# LCD_Controller.net
KiCad netlist of a schematic drawn in Altium Designer
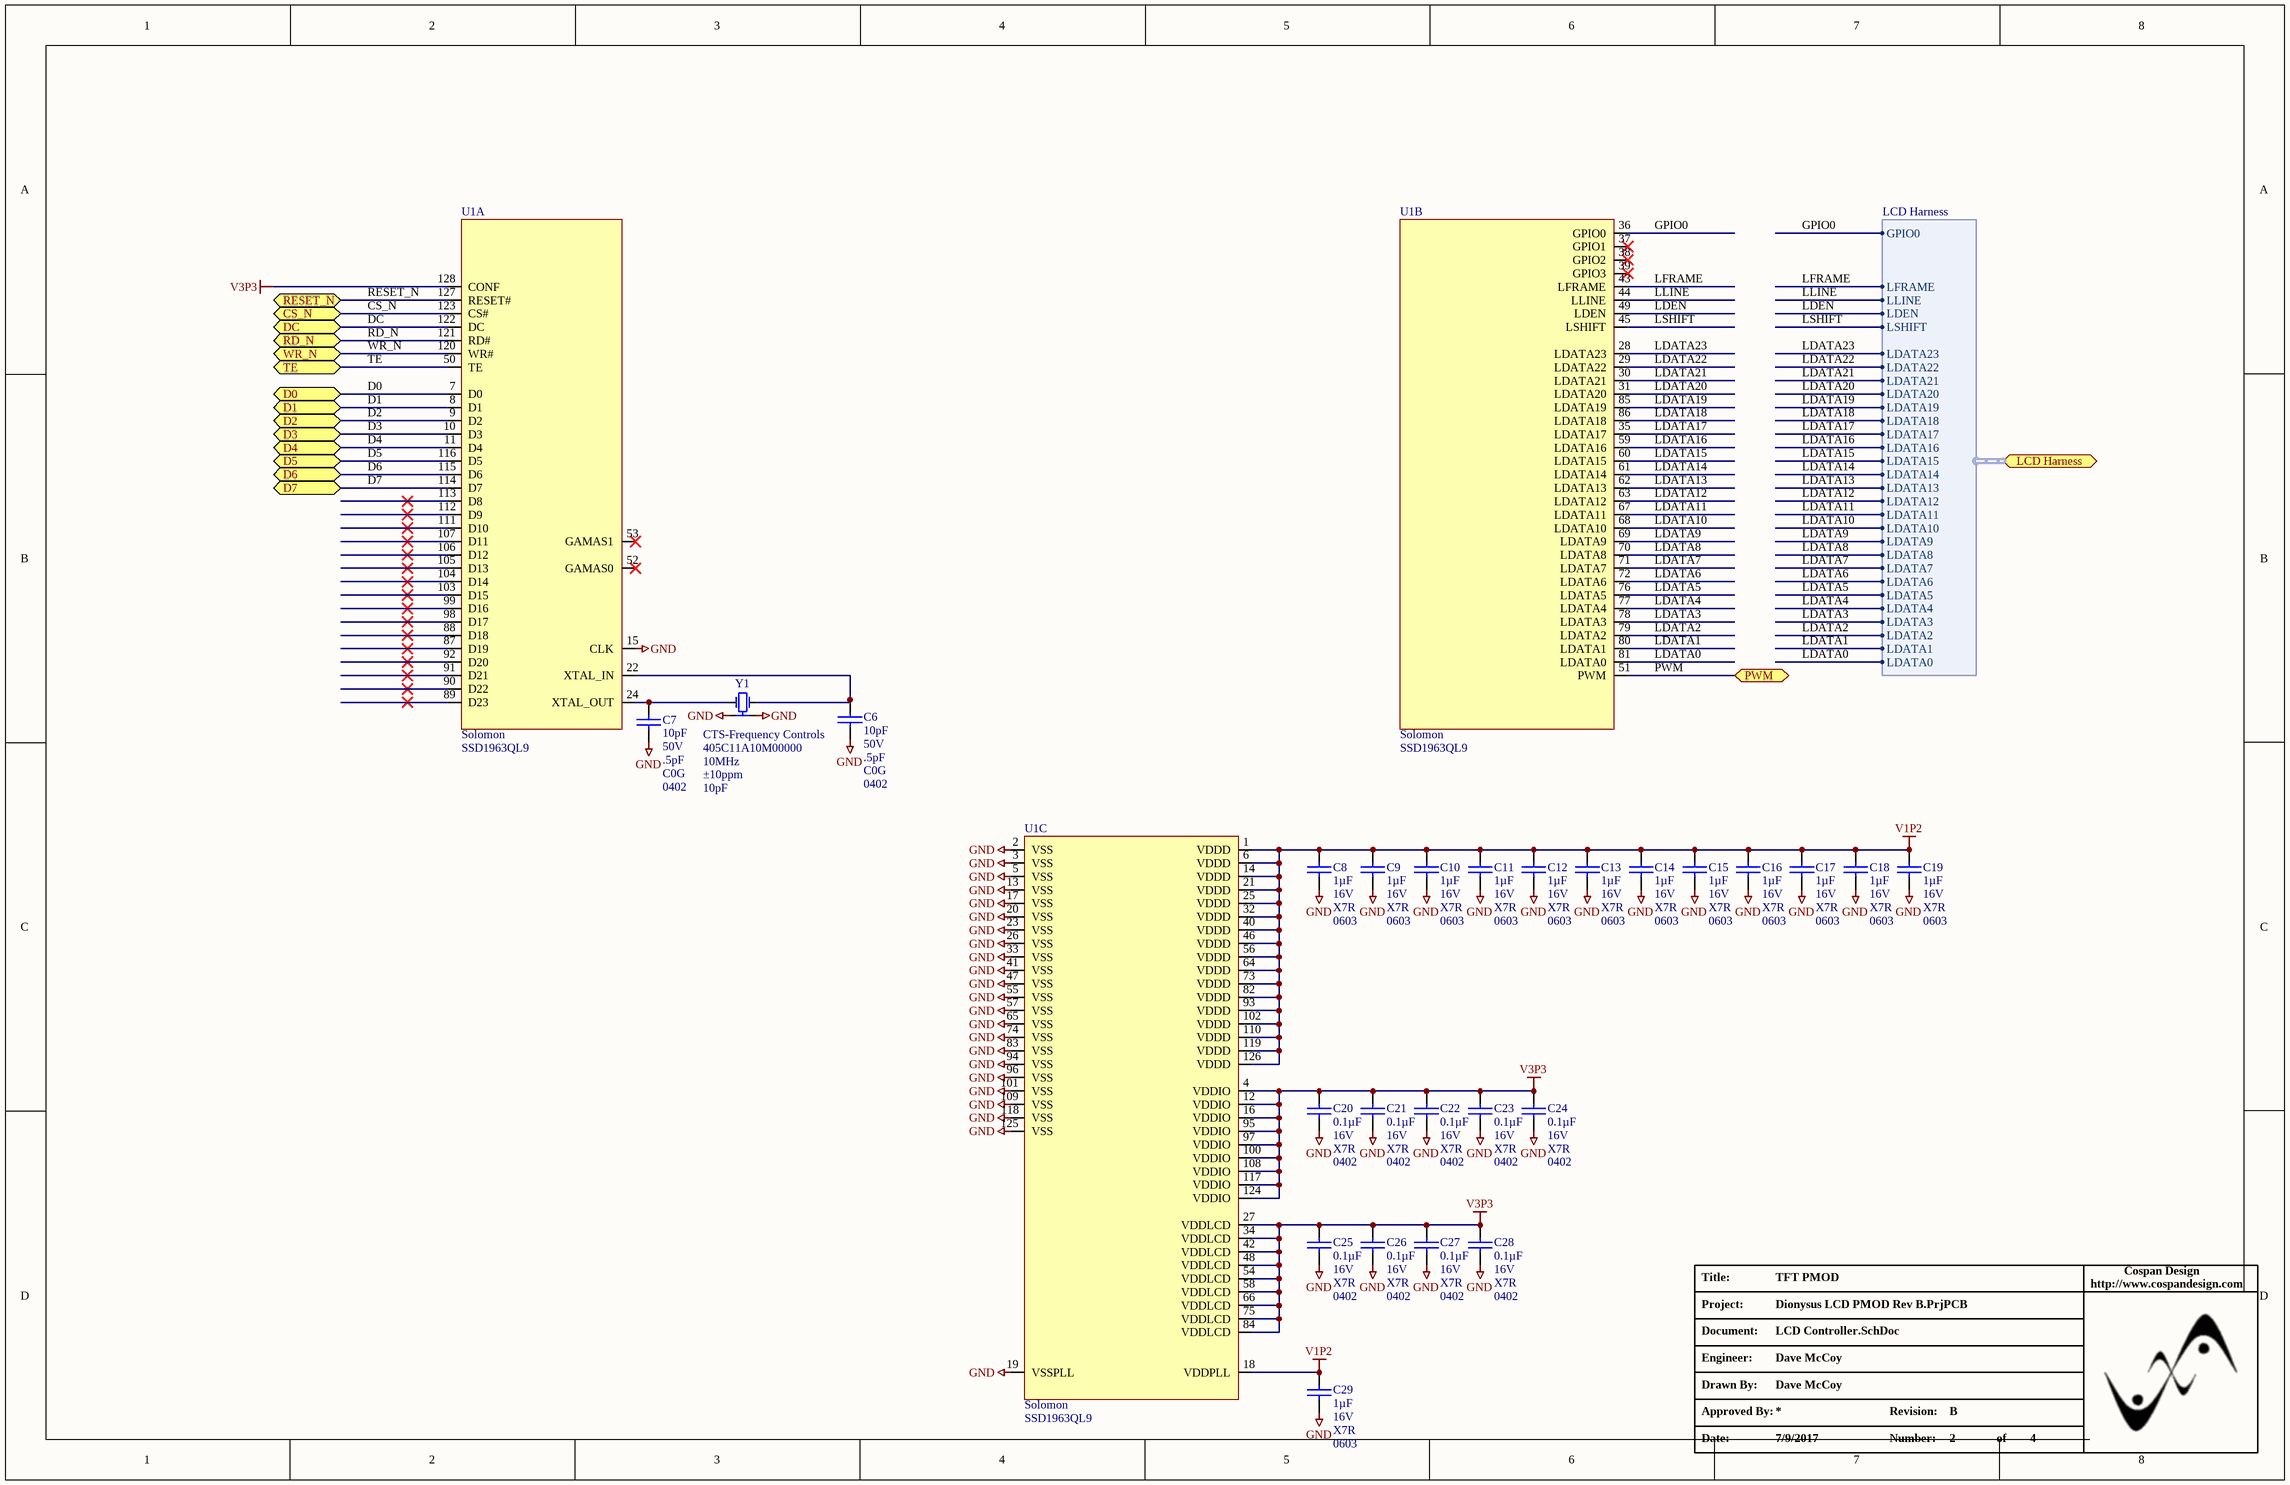
[diagram p0: LCD Controller.SchDoc]

(export (version "E")
  (design (tool "Eeschema 10.0.6"))
  (components
    (comp (ref "C6")
      (value "10pF")
      (footprint "C_ERA-0402")
      (description "CAP CER 10PF 50V NP0 0402")
      (fields
        (field (name "MANUFACTURER") "Taiyo Yuden")
        (field (name "MANUFACTURER PART NUMBER") "UMK105CG100DV-F")
        (field (name "CAPACITANCE") "10pF")
        (field (name "VOLTAGE - RATED") "50V")
        (field (name "TOLERANCE") ".5pF")
        (field (name "TEMPERATURE COEFFICIENT") "C0G")
        (field (name "PACKAGE / CASE") "0402")
      )
      (libsource (lib "Main Library") (part "C_0402_10PF_50V"))
    )
    (comp (ref "C7")
      (value "10pF")
      (footprint "C_ERA-0402")
      (description "CAP CER 10PF 50V NP0 0402")
      (fields
        (field (name "MANUFACTURER") "Taiyo Yuden")
        (field (name "MANUFACTURER PART NUMBER") "UMK105CG100DV-F")
        (field (name "CAPACITANCE") "10pF")
        (field (name "VOLTAGE - RATED") "50V")
        (field (name "TOLERANCE") ".5pF")
        (field (name "TEMPERATURE COEFFICIENT") "C0G")
        (field (name "PACKAGE / CASE") "0402")
      )
      (libsource (lib "Main Library") (part "C_0402_10PF_50V"))
    )
    (comp (ref "C8")
      (value "C_0603_1µF_16V")
      (footprint "C_ERA-0603")
      (description "CAP CER 1UF 16V X7R 0603")
      (fields
        (field (name "CAPACITANCE") "1µF")
        (field (name "VOLTAGE - RATED") "16V")
        (field (name "TEMPERATURE COEFFICIENT") "X7R")
        (field (name "PACKAGE / CASE") "0603")
        (field (name "MANUFACTURER") "Yageo")
        (field (name "MANUFACTURER PART NUMBER") "CC0603KRX7R7BB105")
      )
      (libsource (lib "Cospan Design") (part "C_0603_1µF_16V"))
    )
    (comp (ref "C9")
      (value "C_0603_1µF_16V")
      (footprint "C_ERA-0603")
      (description "CAP CER 1UF 16V X7R 0603")
      (fields
        (field (name "CAPACITANCE") "1µF")
        (field (name "VOLTAGE - RATED") "16V")
        (field (name "TEMPERATURE COEFFICIENT") "X7R")
        (field (name "PACKAGE / CASE") "0603")
        (field (name "MANUFACTURER") "Yageo")
        (field (name "MANUFACTURER PART NUMBER") "CC0603KRX7R7BB105")
      )
      (libsource (lib "Cospan Design") (part "C_0603_1µF_16V"))
    )
    (comp (ref "C10")
      (value "C_0603_1µF_16V")
      (footprint "C_ERA-0603")
      (description "CAP CER 1UF 16V X7R 0603")
      (fields
        (field (name "CAPACITANCE") "1µF")
        (field (name "VOLTAGE - RATED") "16V")
        (field (name "TEMPERATURE COEFFICIENT") "X7R")
        (field (name "PACKAGE / CASE") "0603")
        (field (name "MANUFACTURER") "Yageo")
        (field (name "MANUFACTURER PART NUMBER") "CC0603KRX7R7BB105")
      )
      (libsource (lib "Cospan Design") (part "C_0603_1µF_16V"))
    )
    (comp (ref "C11")
      (value "C_0603_1µF_16V")
      (footprint "C_ERA-0603")
      (description "CAP CER 1UF 16V X7R 0603")
      (fields
        (field (name "CAPACITANCE") "1µF")
        (field (name "VOLTAGE - RATED") "16V")
        (field (name "TEMPERATURE COEFFICIENT") "X7R")
        (field (name "PACKAGE / CASE") "0603")
        (field (name "MANUFACTURER") "Yageo")
        (field (name "MANUFACTURER PART NUMBER") "CC0603KRX7R7BB105")
      )
      (libsource (lib "Cospan Design") (part "C_0603_1µF_16V"))
    )
    (comp (ref "C12")
      (value "C_0603_1µF_16V")
      (footprint "C_ERA-0603")
      (description "CAP CER 1UF 16V X7R 0603")
      (fields
        (field (name "CAPACITANCE") "1µF")
        (field (name "VOLTAGE - RATED") "16V")
        (field (name "TEMPERATURE COEFFICIENT") "X7R")
        (field (name "PACKAGE / CASE") "0603")
        (field (name "MANUFACTURER") "Yageo")
        (field (name "MANUFACTURER PART NUMBER") "CC0603KRX7R7BB105")
      )
      (libsource (lib "Cospan Design") (part "C_0603_1µF_16V"))
    )
    (comp (ref "C13")
      (value "C_0603_1µF_16V")
      (footprint "C_ERA-0603")
      (description "CAP CER 1UF 16V X7R 0603")
      (fields
        (field (name "CAPACITANCE") "1µF")
        (field (name "VOLTAGE - RATED") "16V")
        (field (name "TEMPERATURE COEFFICIENT") "X7R")
        (field (name "PACKAGE / CASE") "0603")
        (field (name "MANUFACTURER") "Yageo")
        (field (name "MANUFACTURER PART NUMBER") "CC0603KRX7R7BB105")
      )
      (libsource (lib "Cospan Design") (part "C_0603_1µF_16V"))
    )
    (comp (ref "C14")
      (value "C_0603_1µF_16V")
      (footprint "C_ERA-0603")
      (description "CAP CER 1UF 16V X7R 0603")
      (fields
        (field (name "CAPACITANCE") "1µF")
        (field (name "VOLTAGE - RATED") "16V")
        (field (name "TEMPERATURE COEFFICIENT") "X7R")
        (field (name "PACKAGE / CASE") "0603")
        (field (name "MANUFACTURER") "Yageo")
        (field (name "MANUFACTURER PART NUMBER") "CC0603KRX7R7BB105")
      )
      (libsource (lib "Cospan Design") (part "C_0603_1µF_16V"))
    )
    (comp (ref "C15")
      (value "C_0603_1µF_16V")
      (footprint "C_ERA-0603")
      (description "CAP CER 1UF 16V X7R 0603")
      (fields
        (field (name "CAPACITANCE") "1µF")
        (field (name "VOLTAGE - RATED") "16V")
        (field (name "TEMPERATURE COEFFICIENT") "X7R")
        (field (name "PACKAGE / CASE") "0603")
        (field (name "MANUFACTURER") "Yageo")
        (field (name "MANUFACTURER PART NUMBER") "CC0603KRX7R7BB105")
      )
      (libsource (lib "Cospan Design") (part "C_0603_1µF_16V"))
    )
    (comp (ref "C16")
      (value "C_0603_1µF_16V")
      (footprint "C_ERA-0603")
      (description "CAP CER 1UF 16V X7R 0603")
      (fields
        (field (name "CAPACITANCE") "1µF")
        (field (name "VOLTAGE - RATED") "16V")
        (field (name "TEMPERATURE COEFFICIENT") "X7R")
        (field (name "PACKAGE / CASE") "0603")
        (field (name "MANUFACTURER") "Yageo")
        (field (name "MANUFACTURER PART NUMBER") "CC0603KRX7R7BB105")
      )
      (libsource (lib "Cospan Design") (part "C_0603_1µF_16V"))
    )
    (comp (ref "C17")
      (value "C_0603_1µF_16V")
      (footprint "C_ERA-0603")
      (description "CAP CER 1UF 16V X7R 0603")
      (fields
        (field (name "CAPACITANCE") "1µF")
        (field (name "VOLTAGE - RATED") "16V")
        (field (name "TEMPERATURE COEFFICIENT") "X7R")
        (field (name "PACKAGE / CASE") "0603")
        (field (name "MANUFACTURER") "Yageo")
        (field (name "MANUFACTURER PART NUMBER") "CC0603KRX7R7BB105")
      )
      (libsource (lib "Cospan Design") (part "C_0603_1µF_16V"))
    )
    (comp (ref "C18")
      (value "C_0603_1µF_16V")
      (footprint "C_ERA-0603")
      (description "CAP CER 1UF 16V X7R 0603")
      (fields
        (field (name "CAPACITANCE") "1µF")
        (field (name "VOLTAGE - RATED") "16V")
        (field (name "TEMPERATURE COEFFICIENT") "X7R")
        (field (name "PACKAGE / CASE") "0603")
        (field (name "MANUFACTURER") "Yageo")
        (field (name "MANUFACTURER PART NUMBER") "CC0603KRX7R7BB105")
      )
      (libsource (lib "Cospan Design") (part "C_0603_1µF_16V"))
    )
    (comp (ref "C19")
      (value "C_0603_1µF_16V")
      (footprint "C_ERA-0603")
      (description "CAP CER 1UF 16V X7R 0603")
      (fields
        (field (name "CAPACITANCE") "1µF")
        (field (name "VOLTAGE - RATED") "16V")
        (field (name "TEMPERATURE COEFFICIENT") "X7R")
        (field (name "PACKAGE / CASE") "0603")
        (field (name "MANUFACTURER") "Yageo")
        (field (name "MANUFACTURER PART NUMBER") "CC0603KRX7R7BB105")
      )
      (libsource (lib "Cospan Design") (part "C_0603_1µF_16V"))
    )
    (comp (ref "C20")
      (value "0.1uF")
      (footprint "C_0402")
      (description "CAP CER .10UF 16V X7R 0402")
      (fields
        (field (name "MANUFACTURER") "TDK Corporation")
        (field (name "MANUFACTURER PART NUMBER") "C1005X7R1C104K050BC")
        (field (name "CAPACITANCE") "0.1µF")
        (field (name "VOLTAGE - RATED") "16V")
        (field (name "TEMPERATURE COEFFICIENT") "X7R")
        (field (name "PACKAGE / CASE") "0402")
      )
      (libsource (lib "Main LibraryX") (part "C_0402_0.1UF_16V"))
    )
    (comp (ref "C21")
      (value "0.1uF")
      (footprint "C_0402")
      (description "CAP CER .10UF 16V X7R 0402")
      (fields
        (field (name "MANUFACTURER") "TDK Corporation")
        (field (name "MANUFACTURER PART NUMBER") "C1005X7R1C104K050BC")
        (field (name "CAPACITANCE") "0.1µF")
        (field (name "VOLTAGE - RATED") "16V")
        (field (name "TEMPERATURE COEFFICIENT") "X7R")
        (field (name "PACKAGE / CASE") "0402")
      )
      (libsource (lib "Main LibraryX") (part "C_0402_0.1UF_16V"))
    )
    (comp (ref "C22")
      (value "0.1uF")
      (footprint "C_0402")
      (description "CAP CER .10UF 16V X7R 0402")
      (fields
        (field (name "MANUFACTURER") "TDK Corporation")
        (field (name "MANUFACTURER PART NUMBER") "C1005X7R1C104K050BC")
        (field (name "CAPACITANCE") "0.1µF")
        (field (name "VOLTAGE - RATED") "16V")
        (field (name "TEMPERATURE COEFFICIENT") "X7R")
        (field (name "PACKAGE / CASE") "0402")
      )
      (libsource (lib "Main LibraryX") (part "C_0402_0.1UF_16V"))
    )
    (comp (ref "C23")
      (value "0.1uF")
      (footprint "C_0402")
      (description "CAP CER .10UF 16V X7R 0402")
      (fields
        (field (name "MANUFACTURER") "TDK Corporation")
        (field (name "MANUFACTURER PART NUMBER") "C1005X7R1C104K050BC")
        (field (name "CAPACITANCE") "0.1µF")
        (field (name "VOLTAGE - RATED") "16V")
        (field (name "TEMPERATURE COEFFICIENT") "X7R")
        (field (name "PACKAGE / CASE") "0402")
      )
      (libsource (lib "Main LibraryX") (part "C_0402_0.1UF_16V"))
    )
    (comp (ref "C24")
      (value "0.1uF")
      (footprint "C_0402")
      (description "CAP CER .10UF 16V X7R 0402")
      (fields
        (field (name "MANUFACTURER") "TDK Corporation")
        (field (name "MANUFACTURER PART NUMBER") "C1005X7R1C104K050BC")
        (field (name "CAPACITANCE") "0.1µF")
        (field (name "VOLTAGE - RATED") "16V")
        (field (name "TEMPERATURE COEFFICIENT") "X7R")
        (field (name "PACKAGE / CASE") "0402")
      )
      (libsource (lib "Main LibraryX") (part "C_0402_0.1UF_16V"))
    )
    (comp (ref "C25")
      (value "0.1uF")
      (footprint "C_0402")
      (description "CAP CER .10UF 16V X7R 0402")
      (fields
        (field (name "MANUFACTURER") "TDK Corporation")
        (field (name "MANUFACTURER PART NUMBER") "C1005X7R1C104K050BC")
        (field (name "CAPACITANCE") "0.1µF")
        (field (name "VOLTAGE - RATED") "16V")
        (field (name "TEMPERATURE COEFFICIENT") "X7R")
        (field (name "PACKAGE / CASE") "0402")
      )
      (libsource (lib "Main LibraryX") (part "C_0402_0.1UF_16V"))
    )
    (comp (ref "C26")
      (value "0.1uF")
      (footprint "C_0402")
      (description "CAP CER .10UF 16V X7R 0402")
      (fields
        (field (name "MANUFACTURER") "TDK Corporation")
        (field (name "MANUFACTURER PART NUMBER") "C1005X7R1C104K050BC")
        (field (name "CAPACITANCE") "0.1µF")
        (field (name "VOLTAGE - RATED") "16V")
        (field (name "TEMPERATURE COEFFICIENT") "X7R")
        (field (name "PACKAGE / CASE") "0402")
      )
      (libsource (lib "Main LibraryX") (part "C_0402_0.1UF_16V"))
    )
    (comp (ref "C27")
      (value "0.1uF")
      (footprint "C_0402")
      (description "CAP CER .10UF 16V X7R 0402")
      (fields
        (field (name "MANUFACTURER") "TDK Corporation")
        (field (name "MANUFACTURER PART NUMBER") "C1005X7R1C104K050BC")
        (field (name "CAPACITANCE") "0.1µF")
        (field (name "VOLTAGE - RATED") "16V")
        (field (name "TEMPERATURE COEFFICIENT") "X7R")
        (field (name "PACKAGE / CASE") "0402")
      )
      (libsource (lib "Main LibraryX") (part "C_0402_0.1UF_16V"))
    )
    (comp (ref "C28")
      (value "0.1uF")
      (footprint "C_0402")
      (description "CAP CER .10UF 16V X7R 0402")
      (fields
        (field (name "MANUFACTURER") "TDK Corporation")
        (field (name "MANUFACTURER PART NUMBER") "C1005X7R1C104K050BC")
        (field (name "CAPACITANCE") "0.1µF")
        (field (name "VOLTAGE - RATED") "16V")
        (field (name "TEMPERATURE COEFFICIENT") "X7R")
        (field (name "PACKAGE / CASE") "0402")
      )
      (libsource (lib "Main LibraryX") (part "C_0402_0.1UF_16V"))
    )
    (comp (ref "C29")
      (value "C_0603_1µF_16V")
      (footprint "C_ERA-0603")
      (description "CAP CER 1UF 16V X7R 0603")
      (fields
        (field (name "CAPACITANCE") "1µF")
        (field (name "VOLTAGE - RATED") "16V")
        (field (name "TEMPERATURE COEFFICIENT") "X7R")
        (field (name "PACKAGE / CASE") "0603")
        (field (name "MANUFACTURER") "Yageo")
        (field (name "MANUFACTURER PART NUMBER") "CC0603KRX7R7BB105")
      )
      (libsource (lib "Cospan Design") (part "C_0603_1µF_16V"))
    )
    (comp (ref "U1")
      (value "U_SSD1963QL9")
      (footprint "LQFP128")
      (description "SSD1963QL9")
      (fields (field (name "MANUFACTURER") "Solomon") (field (name "MANUFACTURER PART NUMBER") "SSD1963QL9"))
      (libsource (lib "Main LibraryX") (part "U_SSD1963QL9"))
    )
    (comp (ref "Y1")
      (value "Y_SMD_10.00MHZ_10PF")
      (footprint "SMD_OSC_8MHZ")
      (description "CRYSTAL 10MHZ 10PF SMD")
      (fields
        (field (name "MANUFACTURER") "CTS-Frequency Controls")
        (field (name "MANUFACTURER PART NUMBER") "405C11A10M00000")
        (field (name "FREQUENCY") "10MHz")
        (field (name "FREQUENCY STABILITY") "±10ppm")
        (field (name "LOAD CAPACITANCE") "10pF")
      )
      (libsource (lib "Main Library") (part "Y_SMD_10.00MHZ_10PF"))
    )
  )
  (nets
    (net (code "3") (name "/CS_N") (class "Default")
      (node (ref "U1") (pin "123") (pinfunction "CS#_123") (pintype "passive"))
    )
    (net (code "4") (name "/D0") (class "Default")
      (node (ref "U1") (pin "7") (pinfunction "D0_7") (pintype "passive"))
    )
    (net (code "5") (name "/D1") (class "Default")
      (node (ref "U1") (pin "8") (pinfunction "D1_8") (pintype "passive"))
    )
    (net (code "6") (name "/D2") (class "Default")
      (node (ref "U1") (pin "9") (pinfunction "D2_9") (pintype "passive"))
    )
    (net (code "7") (name "/D3") (class "Default")
      (node (ref "U1") (pin "10") (pinfunction "D3_10") (pintype "passive"))
    )
    (net (code "8") (name "/D4") (class "Default")
      (node (ref "U1") (pin "11") (pinfunction "D4_11") (pintype "passive"))
    )
    (net (code "9") (name "/D5") (class "Default")
      (node (ref "U1") (pin "116") (pinfunction "D5_116") (pintype "passive"))
    )
    (net (code "10") (name "/D6") (class "Default")
      (node (ref "U1") (pin "115") (pinfunction "D6_115") (pintype "passive"))
    )
    (net (code "11") (name "/D7") (class "Default")
      (node (ref "U1") (pin "114") (pinfunction "D7_114") (pintype "passive"))
    )
    (net (code "12") (name "/DC") (class "Default")
      (node (ref "U1") (pin "122") (pinfunction "DC_122") (pintype "passive"))
    )
    (net (code "13") (name "/GPIO0") (class "Default")
      (node (ref "U1") (pin "36") (pinfunction "GPIO0_36") (pintype "passive"))
    )
    (net (code "14") (name "/LDATA0") (class "Default")
      (node (ref "U1") (pin "81") (pinfunction "LDATA0_81") (pintype "passive"))
    )
    (net (code "15") (name "/LDATA1") (class "Default")
      (node (ref "U1") (pin "80") (pinfunction "LDATA1_80") (pintype "passive"))
    )
    (net (code "16") (name "/LDATA2") (class "Default")
      (node (ref "U1") (pin "79") (pinfunction "LDATA2_79") (pintype "passive"))
    )
    (net (code "17") (name "/LDATA3") (class "Default")
      (node (ref "U1") (pin "78") (pinfunction "LDATA3_78") (pintype "passive"))
    )
    (net (code "18") (name "/LDATA4") (class "Default")
      (node (ref "U1") (pin "77") (pinfunction "LDATA4_77") (pintype "passive"))
    )
    (net (code "19") (name "/LDATA5") (class "Default")
      (node (ref "U1") (pin "76") (pinfunction "LDATA5_76") (pintype "passive"))
    )
    (net (code "20") (name "/LDATA6") (class "Default")
      (node (ref "U1") (pin "72") (pinfunction "LDATA6_72") (pintype "passive"))
    )
    (net (code "21") (name "/LDATA7") (class "Default")
      (node (ref "U1") (pin "71") (pinfunction "LDATA7_71") (pintype "passive"))
    )
    (net (code "22") (name "/LDATA8") (class "Default")
      (node (ref "U1") (pin "70") (pinfunction "LDATA8_70") (pintype "passive"))
    )
    (net (code "23") (name "/LDATA9") (class "Default")
      (node (ref "U1") (pin "69") (pinfunction "LDATA9_69") (pintype "passive"))
    )
    (net (code "24") (name "/LDATA10") (class "Default")
      (node (ref "U1") (pin "68") (pinfunction "LDATA10_68") (pintype "passive"))
    )
    (net (code "25") (name "/LDATA11") (class "Default")
      (node (ref "U1") (pin "67") (pinfunction "LDATA11_67") (pintype "passive"))
    )
    (net (code "26") (name "/LDATA12") (class "Default")
      (node (ref "U1") (pin "63") (pinfunction "LDATA12_63") (pintype "passive"))
    )
    (net (code "27") (name "/LDATA13") (class "Default")
      (node (ref "U1") (pin "62") (pinfunction "LDATA13_62") (pintype "passive"))
    )
    (net (code "28") (name "/LDATA14") (class "Default")
      (node (ref "U1") (pin "61") (pinfunction "LDATA14_61") (pintype "passive"))
    )
    (net (code "29") (name "/LDATA15") (class "Default")
      (node (ref "U1") (pin "60") (pinfunction "LDATA15_60") (pintype "passive"))
    )
    (net (code "30") (name "/LDATA16") (class "Default")
      (node (ref "U1") (pin "59") (pinfunction "LDATA16_59") (pintype "passive"))
    )
    (net (code "31") (name "/LDATA17") (class "Default")
      (node (ref "U1") (pin "35") (pinfunction "LDATA17_35") (pintype "passive"))
    )
    (net (code "32") (name "/LDATA18") (class "Default")
      (node (ref "U1") (pin "86") (pinfunction "LDATA18_86") (pintype "passive"))
    )
    (net (code "33") (name "/LDATA19") (class "Default")
      (node (ref "U1") (pin "85") (pinfunction "LDATA19_85") (pintype "passive"))
    )
    (net (code "34") (name "/LDATA20") (class "Default")
      (node (ref "U1") (pin "31") (pinfunction "LDATA20_31") (pintype "passive"))
    )
    (net (code "35") (name "/LDATA21") (class "Default")
      (node (ref "U1") (pin "30") (pinfunction "LDATA21_30") (pintype "passive"))
    )
    (net (code "36") (name "/LDATA22") (class "Default")
      (node (ref "U1") (pin "29") (pinfunction "LDATA22_29") (pintype "passive"))
    )
    (net (code "37") (name "/LDATA23") (class "Default")
      (node (ref "U1") (pin "28") (pinfunction "LDATA23_28") (pintype "passive"))
    )
    (net (code "38") (name "/LDEN") (class "Default")
      (node (ref "U1") (pin "49") (pinfunction "LDEN_49") (pintype "passive"))
    )
    (net (code "39") (name "/LFRAME") (class "Default")
      (node (ref "U1") (pin "43") (pinfunction "LFRAME_43") (pintype "passive"))
    )
    (net (code "40") (name "/LLINE") (class "Default")
      (node (ref "U1") (pin "44") (pinfunction "LLINE_44") (pintype "passive"))
    )
    (net (code "41") (name "/LSHIFT") (class "Default")
      (node (ref "U1") (pin "45") (pinfunction "LSHIFT_45") (pintype "passive"))
    )
    (net (code "42") (name "/PWM") (class "Default")
      (node (ref "U1") (pin "51") (pinfunction "PWM_51") (pintype "passive"))
    )
    (net (code "43") (name "/RD_N") (class "Default")
      (node (ref "U1") (pin "121") (pinfunction "RD#_121") (pintype "passive"))
    )
    (net (code "44") (name "/RESET_N") (class "Default")
      (node (ref "U1") (pin "127") (pinfunction "RESET#_127") (pintype "passive"))
    )
    (net (code "45") (name "/TE") (class "Default")
      (node (ref "U1") (pin "50") (pinfunction "TE_50") (pintype "passive"))
    )
    (net (code "46") (name "/WR_N") (class "Default")
      (node (ref "U1") (pin "120") (pinfunction "WR#_120") (pintype "passive"))
    )
    (net (code "48") (name "GND") (class "Default")
      (node (ref "C10") (pin "1") (pinfunction "1_1") (pintype "passive"))
      (node (ref "C11") (pin "1") (pinfunction "1_1") (pintype "passive"))
      (node (ref "C12") (pin "1") (pinfunction "1_1") (pintype "passive"))
      (node (ref "C13") (pin "1") (pinfunction "1_1") (pintype "passive"))
      (node (ref "C14") (pin "1") (pinfunction "1_1") (pintype "passive"))
      (node (ref "C15") (pin "1") (pinfunction "1_1") (pintype "passive"))
      (node (ref "C16") (pin "1") (pinfunction "1_1") (pintype "passive"))
      (node (ref "C17") (pin "1") (pinfunction "1_1") (pintype "passive"))
      (node (ref "C18") (pin "1") (pinfunction "1_1") (pintype "passive"))
      (node (ref "C19") (pin "1") (pinfunction "1_1") (pintype "passive"))
      (node (ref "C20") (pin "1") (pinfunction "1_1") (pintype "passive"))
      (node (ref "C21") (pin "1") (pinfunction "1_1") (pintype "passive"))
      (node (ref "C22") (pin "1") (pinfunction "1_1") (pintype "passive"))
      (node (ref "C23") (pin "1") (pinfunction "1_1") (pintype "passive"))
      (node (ref "C24") (pin "1") (pinfunction "1_1") (pintype "passive"))
      (node (ref "C25") (pin "1") (pinfunction "1_1") (pintype "passive"))
      (node (ref "C26") (pin "1") (pinfunction "1_1") (pintype "passive"))
      (node (ref "C27") (pin "1") (pinfunction "1_1") (pintype "passive"))
      (node (ref "C28") (pin "1") (pinfunction "1_1") (pintype "passive"))
      (node (ref "C29") (pin "1") (pinfunction "1_1") (pintype "passive"))
      (node (ref "C6") (pin "1") (pinfunction "1_1") (pintype "passive"))
      (node (ref "C7") (pin "1") (pinfunction "1_1") (pintype "passive"))
      (node (ref "C8") (pin "1") (pinfunction "1_1") (pintype "passive"))
      (node (ref "C9") (pin "1") (pinfunction "1_1") (pintype "passive"))
      (node (ref "U1") (pin "101") (pinfunction "VSS_101") (pintype "passive"))
      (node (ref "U1") (pin "109") (pinfunction "VSS_109") (pintype "passive"))
      (node (ref "U1") (pin "118") (pinfunction "VSS_118") (pintype "passive"))
      (node (ref "U1") (pin "125") (pinfunction "VSS_125") (pintype "passive"))
      (node (ref "U1") (pin "13") (pinfunction "VSS_13") (pintype "passive"))
      (node (ref "U1") (pin "15") (pinfunction "CLK_15") (pintype "passive"))
      (node (ref "U1") (pin "17") (pinfunction "VSS_17") (pintype "passive"))
      (node (ref "U1") (pin "19") (pinfunction "VSSPLL_19") (pintype "passive"))
      (node (ref "U1") (pin "2") (pinfunction "VSS_2") (pintype "passive"))
      (node (ref "U1") (pin "20") (pinfunction "VSS_20") (pintype "passive"))
      (node (ref "U1") (pin "23") (pinfunction "VSS_23") (pintype "passive"))
      (node (ref "U1") (pin "26") (pinfunction "VSS_26") (pintype "passive"))
      (node (ref "U1") (pin "3") (pinfunction "VSS_3") (pintype "passive"))
      (node (ref "U1") (pin "33") (pinfunction "VSS_33") (pintype "passive"))
      (node (ref "U1") (pin "41") (pinfunction "VSS_41") (pintype "passive"))
      (node (ref "U1") (pin "47") (pinfunction "VSS_47") (pintype "passive"))
      (node (ref "U1") (pin "5") (pinfunction "VSS_5") (pintype "passive"))
      (node (ref "U1") (pin "55") (pinfunction "VSS_55") (pintype "passive"))
      (node (ref "U1") (pin "57") (pinfunction "VSS_57") (pintype "passive"))
      (node (ref "U1") (pin "65") (pinfunction "VSS_65") (pintype "passive"))
      (node (ref "U1") (pin "74") (pinfunction "VSS_74") (pintype "passive"))
      (node (ref "U1") (pin "83") (pinfunction "VSS_83") (pintype "passive"))
      (node (ref "U1") (pin "94") (pinfunction "VSS_94") (pintype "passive"))
      (node (ref "U1") (pin "96") (pinfunction "VSS_96") (pintype "passive"))
      (node (ref "Y1") (pin "2") (pinfunction "2_2") (pintype "passive"))
      (node (ref "Y1") (pin "4") (pinfunction "4_4") (pintype "passive"))
    )
    (net (code "49") (name "Net-(U1A-XTAL_IN)") (class "Default")
      (node (ref "C6") (pin "2") (pinfunction "2_2") (pintype "passive"))
      (node (ref "U1") (pin "22") (pinfunction "XTAL_IN_22") (pintype "passive"))
      (node (ref "Y1") (pin "3") (pinfunction "3_3") (pintype "passive"))
    )
    (net (code "50") (name "Net-(U1A-XTAL_OUT)") (class "Default")
      (node (ref "C7") (pin "2") (pinfunction "2_2") (pintype "passive"))
      (node (ref "U1") (pin "24") (pinfunction "XTAL_OUT_24") (pintype "passive"))
      (node (ref "Y1") (pin "1") (pinfunction "1_1") (pintype "passive"))
    )
    (net (code "51") (name "V1P2") (class "Default")
      (node (ref "C10") (pin "2") (pinfunction "2_2") (pintype "passive"))
      (node (ref "C11") (pin "2") (pinfunction "2_2") (pintype "passive"))
      (node (ref "C12") (pin "2") (pinfunction "2_2") (pintype "passive"))
      (node (ref "C13") (pin "2") (pinfunction "2_2") (pintype "passive"))
      (node (ref "C14") (pin "2") (pinfunction "2_2") (pintype "passive"))
      (node (ref "C15") (pin "2") (pinfunction "2_2") (pintype "passive"))
      (node (ref "C16") (pin "2") (pinfunction "2_2") (pintype "passive"))
      (node (ref "C17") (pin "2") (pinfunction "2_2") (pintype "passive"))
      (node (ref "C18") (pin "2") (pinfunction "2_2") (pintype "passive"))
      (node (ref "C19") (pin "2") (pinfunction "2_2") (pintype "passive"))
      (node (ref "C29") (pin "2") (pinfunction "2_2") (pintype "passive"))
      (node (ref "C8") (pin "2") (pinfunction "2_2") (pintype "passive"))
      (node (ref "C9") (pin "2") (pinfunction "2_2") (pintype "passive"))
      (node (ref "U1") (pin "1") (pinfunction "VDDD_1") (pintype "passive"))
      (node (ref "U1") (pin "102") (pinfunction "VDDD_102") (pintype "passive"))
      (node (ref "U1") (pin "110") (pinfunction "VDDD_110") (pintype "passive"))
      (node (ref "U1") (pin "119") (pinfunction "VDDD_119") (pintype "passive"))
      (node (ref "U1") (pin "126") (pinfunction "VDDD_126") (pintype "passive"))
      (node (ref "U1") (pin "14") (pinfunction "VDDD_14") (pintype "passive"))
      (node (ref "U1") (pin "18") (pinfunction "VDDPLL_18") (pintype "passive"))
      (node (ref "U1") (pin "21") (pinfunction "VDDD_21") (pintype "passive"))
      (node (ref "U1") (pin "25") (pinfunction "VDDD_25") (pintype "passive"))
      (node (ref "U1") (pin "32") (pinfunction "VDDD_32") (pintype "passive"))
      (node (ref "U1") (pin "40") (pinfunction "VDDD_40") (pintype "passive"))
      (node (ref "U1") (pin "46") (pinfunction "VDDD_46") (pintype "passive"))
      (node (ref "U1") (pin "56") (pinfunction "VDDD_56") (pintype "passive"))
      (node (ref "U1") (pin "6") (pinfunction "VDDD_6") (pintype "passive"))
      (node (ref "U1") (pin "64") (pinfunction "VDDD_64") (pintype "passive"))
      (node (ref "U1") (pin "73") (pinfunction "VDDD_73") (pintype "passive"))
      (node (ref "U1") (pin "82") (pinfunction "VDDD_82") (pintype "passive"))
      (node (ref "U1") (pin "93") (pinfunction "VDDD_93") (pintype "passive"))
    )
    (net (code "52") (name "V3P3") (class "Default")
      (node (ref "C20") (pin "2") (pinfunction "2_2") (pintype "passive"))
      (node (ref "C21") (pin "2") (pinfunction "2_2") (pintype "passive"))
      (node (ref "C22") (pin "2") (pinfunction "2_2") (pintype "passive"))
      (node (ref "C23") (pin "2") (pinfunction "2_2") (pintype "passive"))
      (node (ref "C24") (pin "2") (pinfunction "2_2") (pintype "passive"))
      (node (ref "C25") (pin "2") (pinfunction "2_2") (pintype "passive"))
      (node (ref "C26") (pin "2") (pinfunction "2_2") (pintype "passive"))
      (node (ref "C27") (pin "2") (pinfunction "2_2") (pintype "passive"))
      (node (ref "C28") (pin "2") (pinfunction "2_2") (pintype "passive"))
      (node (ref "U1") (pin "100") (pinfunction "VDDIO_100") (pintype "passive"))
      (node (ref "U1") (pin "108") (pinfunction "VDDIO_108") (pintype "passive"))
      (node (ref "U1") (pin "117") (pinfunction "VDDIO_117") (pintype "passive"))
      (node (ref "U1") (pin "12") (pinfunction "VDDIO_12") (pintype "passive"))
      (node (ref "U1") (pin "124") (pinfunction "VDDIO_124") (pintype "passive"))
      (node (ref "U1") (pin "128") (pinfunction "CONF_128") (pintype "passive"))
      (node (ref "U1") (pin "16") (pinfunction "VDDIO_16") (pintype "passive"))
      (node (ref "U1") (pin "27") (pinfunction "VDDLCD_27") (pintype "passive"))
      (node (ref "U1") (pin "34") (pinfunction "VDDLCD_34") (pintype "passive"))
      (node (ref "U1") (pin "4") (pinfunction "VDDIO_4") (pintype "passive"))
      (node (ref "U1") (pin "42") (pinfunction "VDDLCD_42") (pintype "passive"))
      (node (ref "U1") (pin "48") (pinfunction "VDDLCD_48") (pintype "passive"))
      (node (ref "U1") (pin "54") (pinfunction "VDDLCD_54") (pintype "passive"))
      (node (ref "U1") (pin "58") (pinfunction "VDDLCD_58") (pintype "passive"))
      (node (ref "U1") (pin "66") (pinfunction "VDDLCD_66") (pintype "passive"))
      (node (ref "U1") (pin "75") (pinfunction "VDDLCD_75") (pintype "passive"))
      (node (ref "U1") (pin "84") (pinfunction "VDDLCD_84") (pintype "passive"))
      (node (ref "U1") (pin "95") (pinfunction "VDDIO_95") (pintype "passive"))
      (node (ref "U1") (pin "97") (pinfunction "VDDIO_97") (pintype "passive"))
    )
    (net (code "53") (name "unconnected-(U1A-D8-Pad113)") (class "Default")
      (node (ref "U1") (pin "113") (pinfunction "D8_113") (pintype "passive"))
    )
    (net (code "54") (name "unconnected-(U1A-D9-Pad112)") (class "Default")
      (node (ref "U1") (pin "112") (pinfunction "D9_112") (pintype "passive"))
    )
    (net (code "55") (name "unconnected-(U1A-D10-Pad111)") (class "Default")
      (node (ref "U1") (pin "111") (pinfunction "D10_111") (pintype "passive"))
    )
    (net (code "56") (name "unconnected-(U1A-D11-Pad107)") (class "Default")
      (node (ref "U1") (pin "107") (pinfunction "D11_107") (pintype "passive"))
    )
    (net (code "57") (name "unconnected-(U1A-D12-Pad106)") (class "Default")
      (node (ref "U1") (pin "106") (pinfunction "D12_106") (pintype "passive"))
    )
    (net (code "58") (name "unconnected-(U1A-D13-Pad105)") (class "Default")
      (node (ref "U1") (pin "105") (pinfunction "D13_105") (pintype "passive"))
    )
    (net (code "59") (name "unconnected-(U1A-D14-Pad104)") (class "Default")
      (node (ref "U1") (pin "104") (pinfunction "D14_104") (pintype "passive"))
    )
    (net (code "60") (name "unconnected-(U1A-D15-Pad103)") (class "Default")
      (node (ref "U1") (pin "103") (pinfunction "D15_103") (pintype "passive"))
    )
    (net (code "61") (name "unconnected-(U1A-D16-Pad99)") (class "Default")
      (node (ref "U1") (pin "99") (pinfunction "D16_99") (pintype "passive"))
    )
    (net (code "62") (name "unconnected-(U1A-D17-Pad98)") (class "Default")
      (node (ref "U1") (pin "98") (pinfunction "D17_98") (pintype "passive"))
    )
    (net (code "63") (name "unconnected-(U1A-D18-Pad88)") (class "Default")
      (node (ref "U1") (pin "88") (pinfunction "D18_88") (pintype "passive"))
    )
    (net (code "64") (name "unconnected-(U1A-D19-Pad87)") (class "Default")
      (node (ref "U1") (pin "87") (pinfunction "D19_87") (pintype "passive"))
    )
    (net (code "65") (name "unconnected-(U1A-D20-Pad92)") (class "Default")
      (node (ref "U1") (pin "92") (pinfunction "D20_92") (pintype "passive"))
    )
    (net (code "66") (name "unconnected-(U1A-D21-Pad91)") (class "Default")
      (node (ref "U1") (pin "91") (pinfunction "D21_91") (pintype "passive"))
    )
    (net (code "67") (name "unconnected-(U1A-D22-Pad90)") (class "Default")
      (node (ref "U1") (pin "90") (pinfunction "D22_90") (pintype "passive"))
    )
    (net (code "68") (name "unconnected-(U1A-D23-Pad89)") (class "Default")
      (node (ref "U1") (pin "89") (pinfunction "D23_89") (pintype "passive"))
    )
    (net (code "69") (name "unconnected-(U1A-GAMAS0-Pad52)") (class "Default")
      (node (ref "U1") (pin "52") (pinfunction "GAMAS0_52") (pintype "passive+no_connect"))
    )
    (net (code "70") (name "unconnected-(U1A-GAMAS1-Pad53)") (class "Default")
      (node (ref "U1") (pin "53") (pinfunction "GAMAS1_53") (pintype "passive+no_connect"))
    )
    (net (code "71") (name "unconnected-(U1B-GPIO1-Pad37)") (class "Default")
      (node (ref "U1") (pin "37") (pinfunction "GPIO1_37") (pintype "passive+no_connect"))
    )
    (net (code "72") (name "unconnected-(U1B-GPIO2-Pad38)") (class "Default")
      (node (ref "U1") (pin "38") (pinfunction "GPIO2_38") (pintype "passive+no_connect"))
    )
    (net (code "73") (name "unconnected-(U1B-GPIO3-Pad39)") (class "Default")
      (node (ref "U1") (pin "39") (pinfunction "GPIO3_39") (pintype "passive+no_connect"))
    )
  )
)
